# AND_NAND_1_1.net
KiCad netlist of a schematic drawn in EAGLE
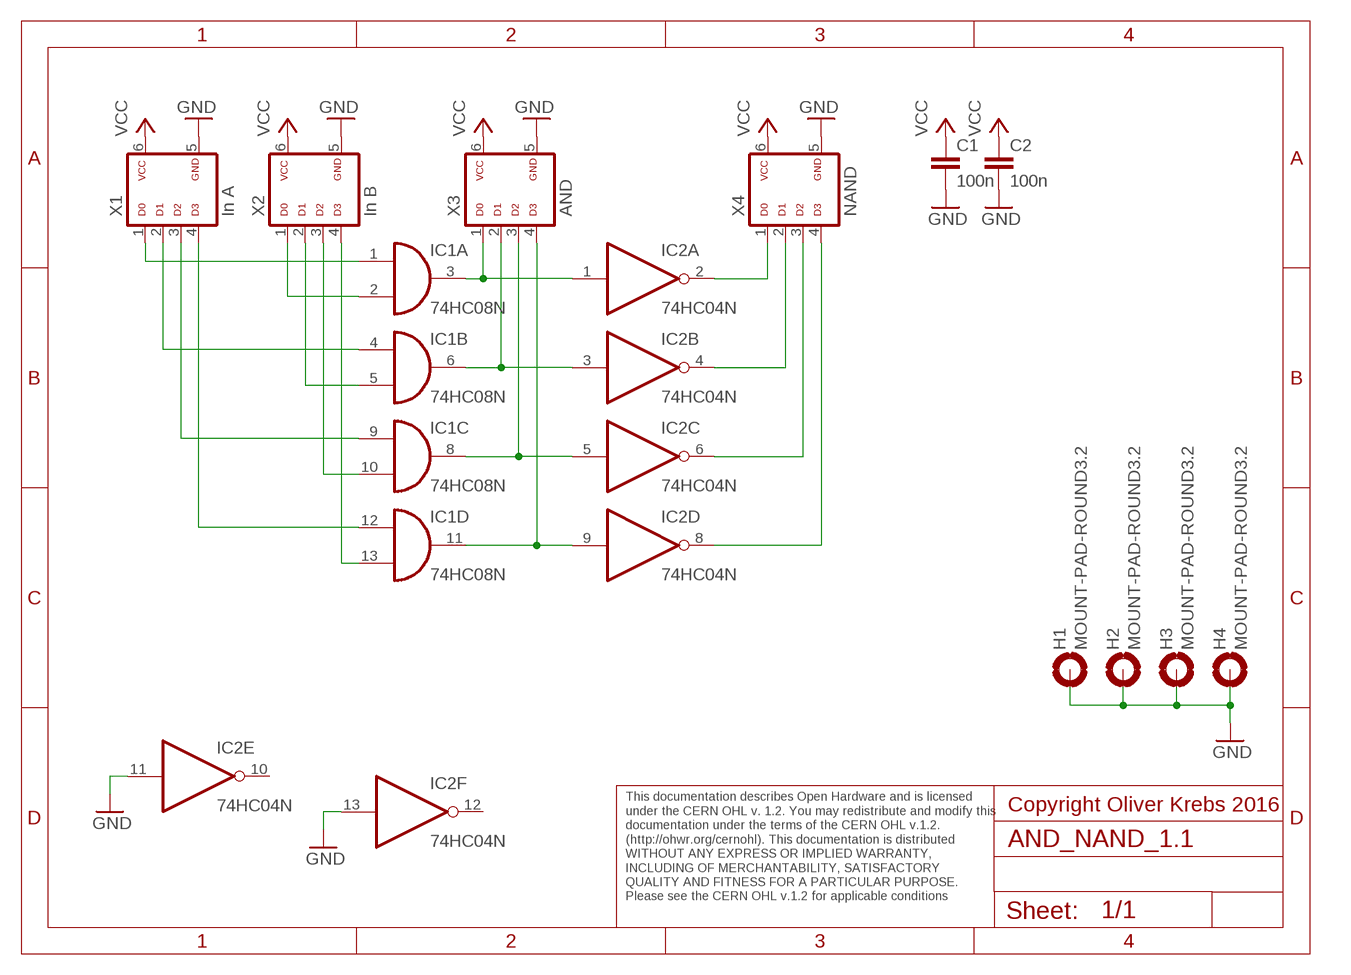
[diagram p0: schematic, sheet 1]

(export (version "E")
  (design (tool "Eeschema 10.0.6"))
  (components
    (comp (ref "C1")
      (value "100n")
      (footprint "eagle-import:C050-025X075")
      (libsource (lib "eagle-import") (part "C-EU050-025X075"))
    )
    (comp (ref "C2")
      (value "100n")
      (footprint "eagle-import:C050-025X075")
      (libsource (lib "eagle-import") (part "C-EU050-025X075"))
    )
    (comp (ref "H1")
      (value "MOUNT-PAD-ROUND3.2")
      (footprint "eagle-import:3,2-PAD")
      (libsource (lib "eagle-import") (part "MOUNT-PAD-ROUND3.2"))
    )
    (comp (ref "H2")
      (value "MOUNT-PAD-ROUND3.2")
      (footprint "eagle-import:3,2-PAD")
      (libsource (lib "eagle-import") (part "MOUNT-PAD-ROUND3.2"))
    )
    (comp (ref "H3")
      (value "MOUNT-PAD-ROUND3.2")
      (footprint "eagle-import:3,2-PAD")
      (libsource (lib "eagle-import") (part "MOUNT-PAD-ROUND3.2"))
    )
    (comp (ref "H4")
      (value "MOUNT-PAD-ROUND3.2")
      (footprint "eagle-import:3,2-PAD")
      (libsource (lib "eagle-import") (part "MOUNT-PAD-ROUND3.2"))
    )
    (comp (ref "IC1")
      (value "74HC08N")
      (footprint "eagle-import:DIL14")
      (libsource (lib "eagle-import") (part "7408NHC"))
    )
    (comp (ref "IC2")
      (value "74HC04N")
      (footprint "eagle-import:DIL14")
      (libsource (lib "eagle-import") (part "7404NHC"))
    )
    (comp (ref "X1")
      (value "In A")
      (footprint "eagle-import:ML-6")
      (libsource (lib "eagle-import") (part "ML6D"))
    )
    (comp (ref "X2")
      (value "In B")
      (footprint "eagle-import:ML-6")
      (libsource (lib "eagle-import") (part "ML6D"))
    )
    (comp (ref "X3")
      (value "AND")
      (footprint "eagle-import:ML-6")
      (libsource (lib "eagle-import") (part "ML6D"))
    )
    (comp (ref "X4")
      (value "NAND")
      (footprint "eagle-import:ML-6")
      (libsource (lib "eagle-import") (part "ML6D"))
    )
  )
  (nets
    (net (code "1") (name "GND") (class "Default")
      (node (ref "C1") (pin "2") (pinfunction "2_2") (pintype "passive"))
      (node (ref "C2") (pin "2") (pinfunction "2_2") (pintype "passive"))
      (node (ref "H1") (pin "B3,2") (pinfunction "MOUNT_B3,2") (pintype "passive"))
      (node (ref "H2") (pin "B3,2") (pinfunction "MOUNT_B3,2") (pintype "passive"))
      (node (ref "H3") (pin "B3,2") (pinfunction "MOUNT_B3,2") (pintype "passive"))
      (node (ref "H4") (pin "B3,2") (pinfunction "MOUNT_B3,2") (pintype "passive"))
      (node (ref "IC2") (pin "11") (pinfunction "I_11") (pintype "input"))
      (node (ref "IC2") (pin "13") (pinfunction "I_13") (pintype "input"))
      (node (ref "X1") (pin "5") (pinfunction "5_5") (pintype "passive"))
      (node (ref "X2") (pin "5") (pinfunction "5_5") (pintype "passive"))
      (node (ref "X3") (pin "5") (pinfunction "5_5") (pintype "passive"))
      (node (ref "X4") (pin "5") (pinfunction "5_5") (pintype "passive"))
    )
    (net (code "2") (name "Net-(IC1A-I0)") (class "Default")
      (node (ref "IC1") (pin "1") (pinfunction "I0_1") (pintype "input"))
      (node (ref "X1") (pin "1") (pinfunction "1_1") (pintype "passive"))
    )
    (net (code "3") (name "Net-(IC1A-I1)") (class "Default")
      (node (ref "IC1") (pin "2") (pinfunction "I1_2") (pintype "input"))
      (node (ref "X2") (pin "1") (pinfunction "1_1") (pintype "passive"))
    )
    (net (code "4") (name "Net-(IC1A-O)") (class "Default")
      (node (ref "IC1") (pin "3") (pinfunction "O_3") (pintype "output"))
      (node (ref "IC2") (pin "1") (pinfunction "I_1") (pintype "input"))
      (node (ref "X3") (pin "1") (pinfunction "1_1") (pintype "passive"))
    )
    (net (code "5") (name "Net-(IC1B-I0)") (class "Default")
      (node (ref "IC1") (pin "4") (pinfunction "I0_4") (pintype "input"))
      (node (ref "X1") (pin "2") (pinfunction "2_2") (pintype "passive"))
    )
    (net (code "6") (name "Net-(IC1B-I1)") (class "Default")
      (node (ref "IC1") (pin "5") (pinfunction "I1_5") (pintype "input"))
      (node (ref "X2") (pin "2") (pinfunction "2_2") (pintype "passive"))
    )
    (net (code "7") (name "Net-(IC1B-O)") (class "Default")
      (node (ref "IC1") (pin "6") (pinfunction "O_6") (pintype "output"))
      (node (ref "IC2") (pin "3") (pinfunction "I_3") (pintype "input"))
      (node (ref "X3") (pin "2") (pinfunction "2_2") (pintype "passive"))
    )
    (net (code "8") (name "Net-(IC1C-I0)") (class "Default")
      (node (ref "IC1") (pin "9") (pinfunction "I0_9") (pintype "input"))
      (node (ref "X1") (pin "3") (pinfunction "3_3") (pintype "passive"))
    )
    (net (code "9") (name "Net-(IC1C-I1)") (class "Default")
      (node (ref "IC1") (pin "10") (pinfunction "I1_10") (pintype "input"))
      (node (ref "X2") (pin "3") (pinfunction "3_3") (pintype "passive"))
    )
    (net (code "10") (name "Net-(IC1C-O)") (class "Default")
      (node (ref "IC1") (pin "8") (pinfunction "O_8") (pintype "output"))
      (node (ref "IC2") (pin "5") (pinfunction "I_5") (pintype "input"))
      (node (ref "X3") (pin "3") (pinfunction "3_3") (pintype "passive"))
    )
    (net (code "11") (name "Net-(IC1D-I0)") (class "Default")
      (node (ref "IC1") (pin "12") (pinfunction "I0_12") (pintype "input"))
      (node (ref "X1") (pin "4") (pinfunction "4_4") (pintype "passive"))
    )
    (net (code "12") (name "Net-(IC1D-I1)") (class "Default")
      (node (ref "IC1") (pin "13") (pinfunction "I1_13") (pintype "input"))
      (node (ref "X2") (pin "4") (pinfunction "4_4") (pintype "passive"))
    )
    (net (code "13") (name "Net-(IC1D-O)") (class "Default")
      (node (ref "IC1") (pin "11") (pinfunction "O_11") (pintype "output"))
      (node (ref "IC2") (pin "9") (pinfunction "I_9") (pintype "input"))
      (node (ref "X3") (pin "4") (pinfunction "4_4") (pintype "passive"))
    )
    (net (code "14") (name "Net-(IC2A-O)") (class "Default")
      (node (ref "IC2") (pin "2") (pinfunction "O_2") (pintype "output"))
      (node (ref "X4") (pin "1") (pinfunction "1_1") (pintype "passive"))
    )
    (net (code "15") (name "Net-(IC2B-O)") (class "Default")
      (node (ref "IC2") (pin "4") (pinfunction "O_4") (pintype "output"))
      (node (ref "X4") (pin "2") (pinfunction "2_2") (pintype "passive"))
    )
    (net (code "16") (name "Net-(IC2C-O)") (class "Default")
      (node (ref "IC2") (pin "6") (pinfunction "O_6") (pintype "output"))
      (node (ref "X4") (pin "3") (pinfunction "3_3") (pintype "passive"))
    )
    (net (code "17") (name "Net-(IC2D-O)") (class "Default")
      (node (ref "IC2") (pin "8") (pinfunction "O_8") (pintype "output"))
      (node (ref "X4") (pin "4") (pinfunction "4_4") (pintype "passive"))
    )
    (net (code "18") (name "VCC") (class "Default")
      (node (ref "C1") (pin "1") (pinfunction "1_1") (pintype "passive"))
      (node (ref "C2") (pin "1") (pinfunction "1_1") (pintype "passive"))
      (node (ref "X1") (pin "6") (pinfunction "6_6") (pintype "passive"))
      (node (ref "X2") (pin "6") (pinfunction "6_6") (pintype "passive"))
      (node (ref "X3") (pin "6") (pinfunction "6_6") (pintype "passive"))
      (node (ref "X4") (pin "6") (pinfunction "6_6") (pintype "passive"))
    )
    (net (code "19") (name "unconnected-(IC2E-O-Pad10)") (class "Default")
      (node (ref "IC2") (pin "10") (pinfunction "O_10") (pintype "output"))
    )
    (net (code "20") (name "unconnected-(IC2F-O-Pad12)") (class "Default")
      (node (ref "IC2") (pin "12") (pinfunction "O_12") (pintype "output"))
    )
  )
)
